# 15_-CLOCK.net
KiCad netlist of a schematic drawn in Altium Designer
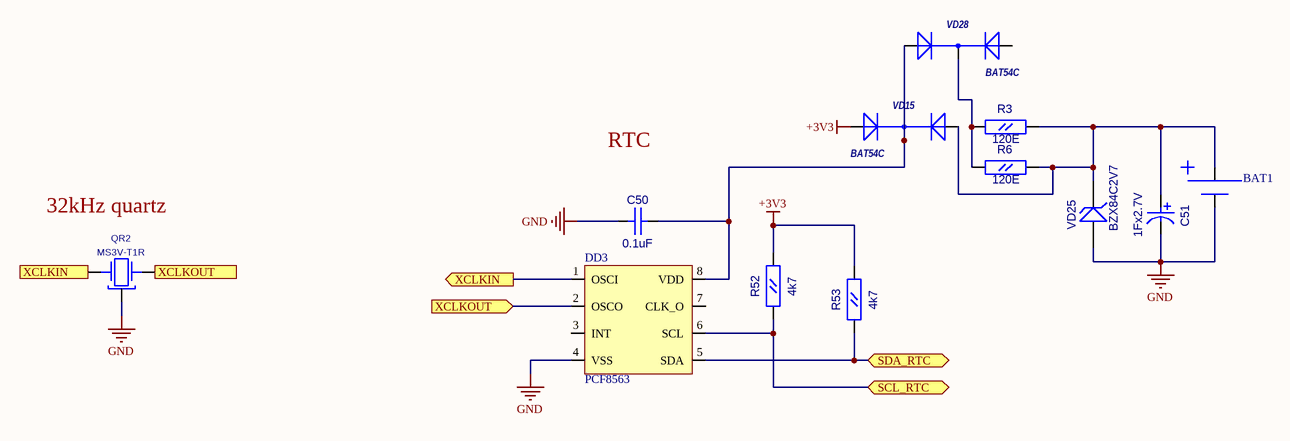
[diagram p0: [15]-CLOCK.SchDoc]

(export (version "E")
  (design (tool "Eeschema 10.0.6"))
  (components
    (comp (ref "BAT1")
      (value "CR2032-VBY4")
      (footprint "CR2032_ONBOARD")
      (libsource (lib "fizik_lib") (part "CR2032-VBY2"))
    )
    (comp (ref "C50")
      (value "0.1uF")
      (footprint "CC0603")
      (description "CC0603")
      (libsource (lib "gprs_modem_2") (part "CC0603"))
    )
    (comp (ref "C51")
      (value "1Fx2.7V")
      (footprint "CC8X11.5_L")
      (description "Radial capacitor")
      (libsource (lib "fizik_lib") (part "CAP_8mm"))
    )
    (comp (ref "DD3") (value "PCF8563") (footprint "SO-8") (libsource (lib "gprs_modem") (part "PCF8563")))
    (comp (ref "QR2")
      (value "MS3V-T1R")
      (footprint "MS3V-T1R")
      (description "CRYSTAL_32768 Hz")
      (libsource (lib "gprs_modem") (part "MS3V-T1R"))
    )
    (comp (ref "R3")
      (value "120E")
      (footprint "RC0805")
      (description "RC0805")
      (libsource (lib "fizik_lib") (part "RC0805"))
    )
    (comp (ref "R6")
      (value "120E")
      (footprint "RC0805")
      (description "RC0805")
      (libsource (lib "fizik_lib") (part "RC0805"))
    )
    (comp (ref "R52")
      (value "4k7")
      (footprint "RC0603")
      (description "RC0603")
      (libsource (lib "gprs_modem_2") (part "RC0603"))
    )
    (comp (ref "R53")
      (value "4k7")
      (footprint "RC0603")
      (description "RC0603")
      (libsource (lib "gprs_modem_2") (part "RC0603"))
    )
    (comp (ref "VD15")
      (value "BAT54C")
      (footprint "SOT-23(123)")
      (libsource (lib "fizik_lib") (part "BAT54C"))
    )
    (comp (ref "VD25")
      (value "BZX84C2V7")
      (footprint "SOT-23(123)")
      (description "Zener Voltage Regulator Diode")
      (libsource (lib "fizik_lib") (part "BZX84"))
    )
    (comp (ref "VD28")
      (value "BAT54C")
      (footprint "SOT-23(123)")
      (libsource (lib "fizik_lib") (part "BAT54C"))
    )
  )
  (nets
    (net (code "1") (name "+3V3") (class "Default")
      (node (ref "R52") (pin "2") (pinfunction "B_2") (pintype "passive"))
      (node (ref "R53") (pin "2") (pinfunction "B_2") (pintype "passive"))
      (node (ref "VD15") (pin "1") (pinfunction "A_1") (pintype "passive"))
    )
    (net (code "2") (name "/SCL_RTC") (class "Default")
      (node (ref "DD3") (pin "6") (pinfunction "SCL_6") (pintype "passive"))
      (node (ref "R52") (pin "1") (pinfunction "A_1") (pintype "passive"))
    )
    (net (code "3") (name "/SDA_RTC") (class "Default")
      (node (ref "DD3") (pin "5") (pinfunction "SDA_5") (pintype "passive"))
      (node (ref "R53") (pin "1") (pinfunction "A_1") (pintype "passive"))
    )
    (net (code "4") (name "/XCLKIN") (class "Default")
      (node (ref "DD3") (pin "1") (pinfunction "OSCI_1") (pintype "passive"))
      (node (ref "QR2") (pin "2") (pinfunction "X2_2") (pintype "passive"))
    )
    (net (code "5") (name "/XCLKOUT") (class "Default")
      (node (ref "DD3") (pin "2") (pinfunction "OSCO_2") (pintype "passive"))
      (node (ref "QR2") (pin "1") (pinfunction "X1_1") (pintype "passive"))
    )
    (net (code "6") (name "GND") (class "Default")
      (node (ref "BAT1") (pin "1") (pintype "passive"))
      (node (ref "C50") (pin "1") (pinfunction "A_1") (pintype "passive"))
      (node (ref "C51") (pin "2") (pintype "passive"))
      (node (ref "DD3") (pin "4") (pinfunction "VSS_4") (pintype "passive"))
      (node (ref "QR2") (pin "3") (pinfunction "3_3") (pintype "passive"))
      (node (ref "VD25") (pin "1") (pinfunction "A_1") (pintype "passive"))
    )
    (net (code "7") (name "Net-(C50-B)") (class "Default")
      (node (ref "C50") (pin "2") (pinfunction "B_2") (pintype "passive"))
      (node (ref "DD3") (pin "8") (pinfunction "VDD_8") (pintype "passive"))
      (node (ref "VD15") (pin "3") (pinfunction "K_3") (pintype "passive"))
      (node (ref "VD28") (pin "1") (pinfunction "A_1") (pintype "passive"))
    )
    (net (code "8") (name "Net-(R3-A)") (class "Default")
      (node (ref "R3") (pin "1") (pinfunction "A_1") (pintype "passive"))
      (node (ref "R6") (pin "1") (pinfunction "A_1") (pintype "passive"))
      (node (ref "VD28") (pin "3") (pinfunction "K_3") (pintype "passive"))
    )
    (net (code "9") (name "Net-(R3-B)") (class "Default")
      (node (ref "BAT1") (pin "2") (pintype "passive"))
      (node (ref "C51") (pin "1") (pintype "passive"))
      (node (ref "R3") (pin "2") (pinfunction "B_2") (pintype "passive"))
      (node (ref "R6") (pin "2") (pinfunction "B_2") (pintype "passive"))
      (node (ref "VD15") (pin "2") (pinfunction "A_2") (pintype "passive"))
      (node (ref "VD25") (pin "3") (pinfunction "K_3") (pintype "passive"))
    )
    (net (code "10") (name "unconnected-(DD3-CLK_O-Pad7)") (class "Default")
      (node (ref "DD3") (pin "7") (pinfunction "CLK_O_7") (pintype "passive"))
    )
    (net (code "11") (name "unconnected-(DD3-INT-Pad3)") (class "Default")
      (node (ref "DD3") (pin "3") (pinfunction "INT_3") (pintype "passive"))
    )
    (net (code "12") (name "unconnected-(VD28-A-Pad2)") (class "Default")
      (node (ref "VD28") (pin "2") (pinfunction "A_2") (pintype "passive"))
    )
  )
)
